# CAN.net
KiCad netlist of a schematic drawn in Altium Designer
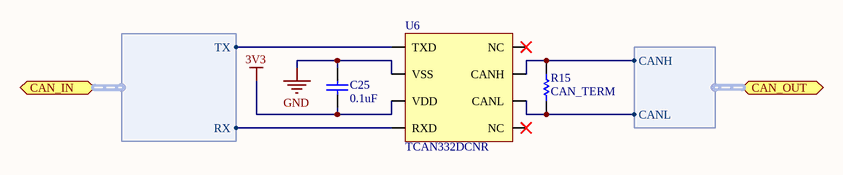
[diagram p0: CAN.SchDoc]

(export (version "E")
  (design (tool "Eeschema 10.0.6"))
  (components
    (comp (ref "C25")
      (value "0.1uF")
      (footprint "CAPC0603(1608)100_L")
      (description "CAP 100nF 100V ±10% 0603 (1608 Metric) Thickness 1mm SMD")
      (fields (field (name "TOLERANCE") "Â±10%"))
      (libsource (lib "Altium Content Vault") (part "CAP"))
    )
    (comp (ref "R15")
      (value "CAN_TERM")
      (footprint "RESC0603(1608)_L")
      (description "120R 0.1W 1% 0603 (1608 Metric)  SMD")
      (fields (field (name "POWER") "0.1 W") (field (name "TOLERANCE") "1 %"))
      (libsource (lib "Altium Content Vault") (part "CMP-1012-00405-1"))
    )
    (comp (ref "U6")
      (value "TCAN332DCNR")
      (footprint "SOT-23-8")
      (description "CAN Interface IC 3.3-V CAN Transceivers with CAN FD (Flexible Data Rate) 8-SOT-23 -40 to 125")
      (fields (field (name "MANUFACTURER") "Texas Instruments"))
      (libsource (lib "ICs") (part "TCAN332DCNR"))
    )
  )
  (nets
    (net (code "3") (name "/CANH") (class "Default")
      (node (ref "R15") (pin "2") (pinfunction "2_2") (pintype "passive"))
      (node (ref "U6") (pin "7") (pinfunction "CANH_7") (pintype "passive"))
    )
    (net (code "4") (name "/CANL") (class "Default")
      (node (ref "R15") (pin "1") (pinfunction "1_1") (pintype "passive"))
      (node (ref "U6") (pin "6") (pinfunction "CANL_6") (pintype "passive"))
    )
    (net (code "5") (name "/RX") (class "Default")
      (node (ref "U6") (pin "4") (pinfunction "RXD_4") (pintype "passive"))
    )
    (net (code "6") (name "/TX") (class "Default")
      (node (ref "U6") (pin "1") (pinfunction "TXD_1") (pintype "passive"))
    )
    (net (code "9") (name "3V3") (class "Default")
      (node (ref "C25") (pin "1") (pinfunction "1_1") (pintype "passive"))
      (node (ref "U6") (pin "3") (pinfunction "VDD_3") (pintype "passive"))
    )
    (net (code "10") (name "GND") (class "Default")
      (node (ref "C25") (pin "2") (pinfunction "2_2") (pintype "passive"))
      (node (ref "U6") (pin "2") (pinfunction "VSS_2") (pintype "passive"))
    )
    (net (code "11") (name "unconnected-(U6-NC-Pad5)") (class "Default")
      (node (ref "U6") (pin "5") (pinfunction "NC_5") (pintype "passive+no_connect"))
    )
    (net (code "12") (name "unconnected-(U6-NC-Pad8)") (class "Default")
      (node (ref "U6") (pin "8") (pinfunction "NC_8") (pintype "passive+no_connect"))
    )
  )
)
